# 2DD-17-mk-2_0.net
KiCad netlist of a schematic drawn in EAGLE
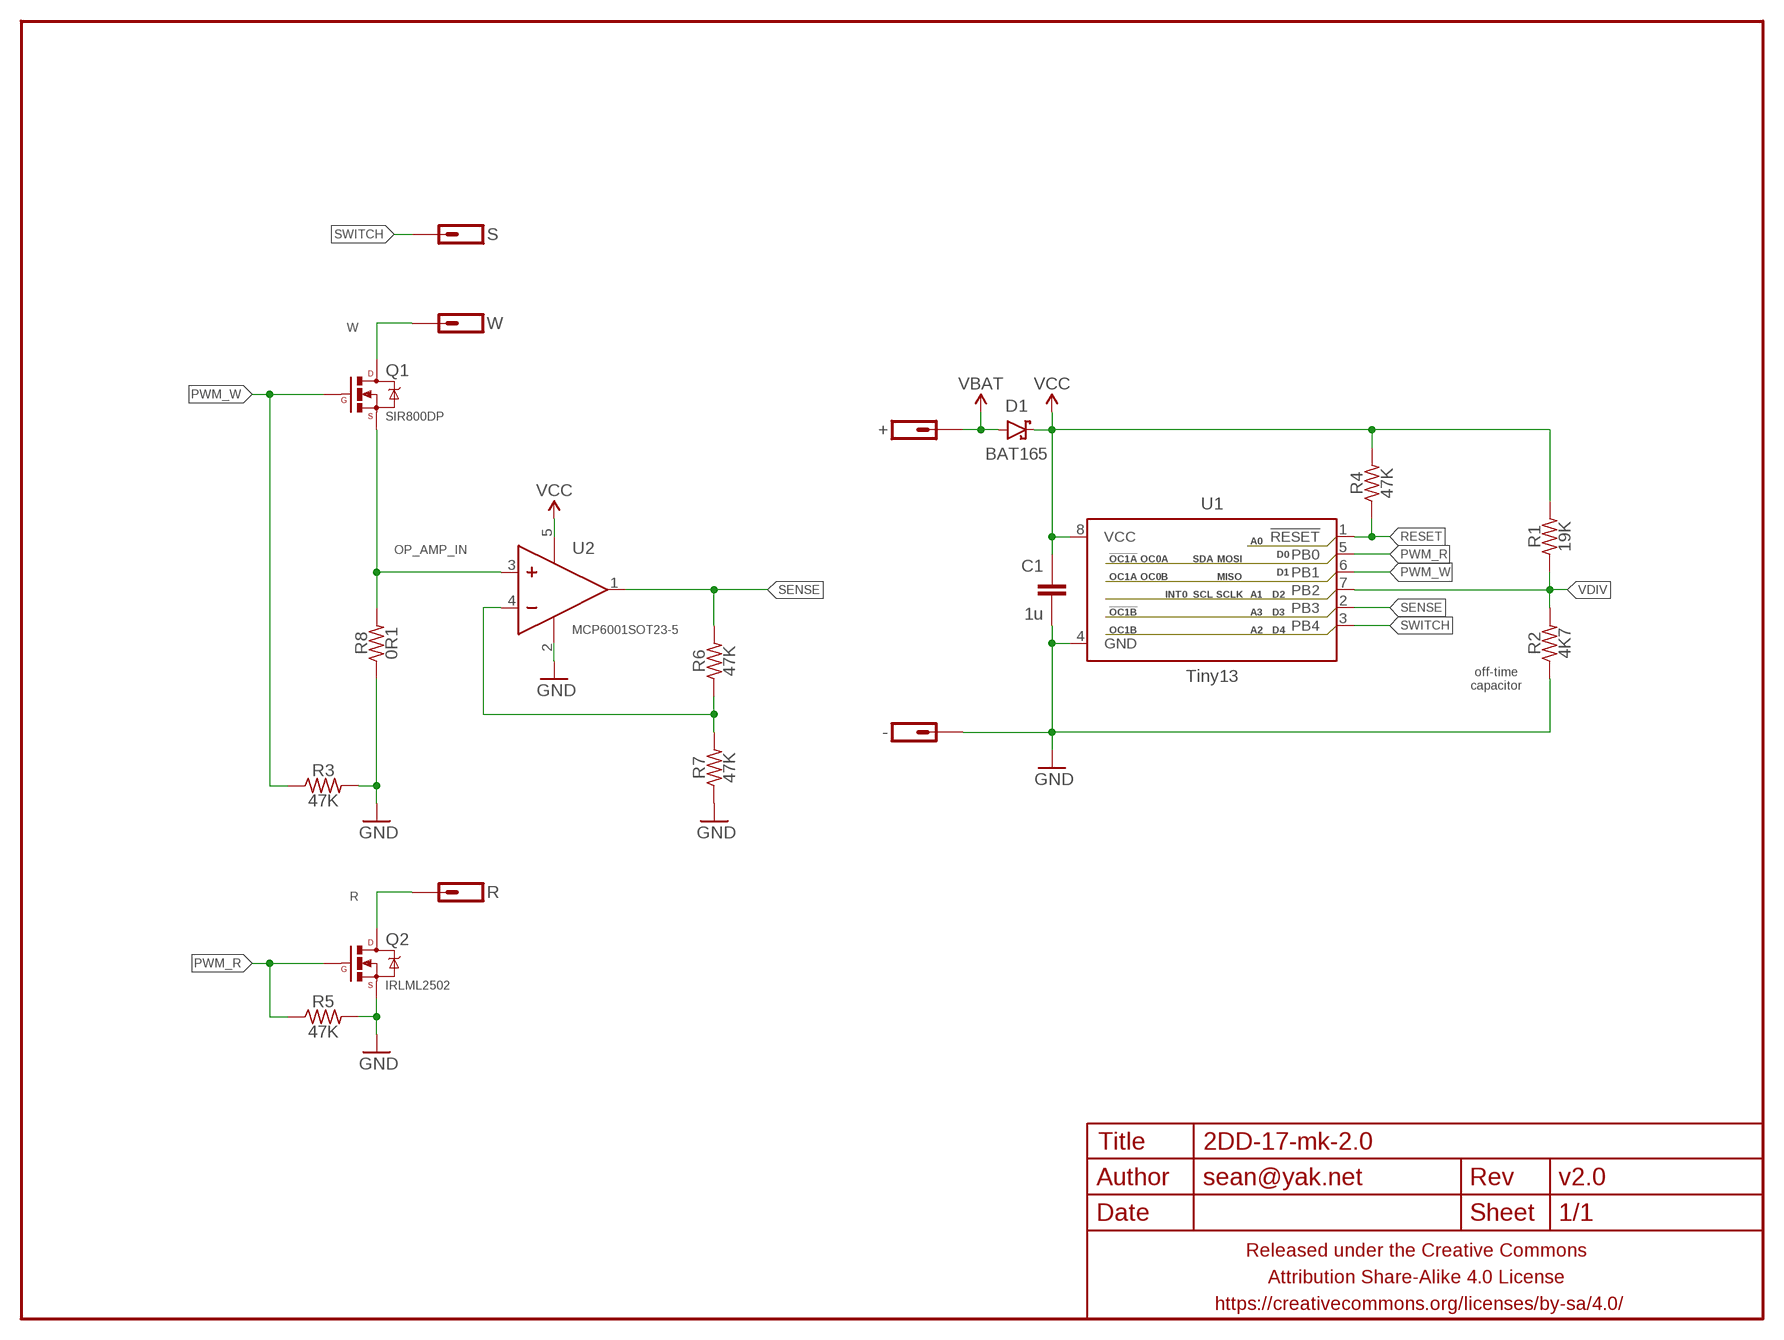
[diagram p0: schematic, sheet 1]

(export (version "E")
  (design (tool "Eeschema 10.0.6"))
  (components
    (comp (ref "+")
      (value "M01PTH-1MM-CIR-NS")
      (footprint "eagle-import:1X01-1MM-CIR-NS")
      (libsource (lib "eagle-import") (part "M01PTH-1MM-CIR-NS"))
    )
    (comp (ref "-")
      (value "M01NOT-A-VIA-NOPE")
      (footprint "eagle-import:1X01_NOSILK_NOSTOP")
      (libsource (lib "eagle-import") (part "M01NOT-A-VIA-NOPE"))
    )
    (comp (ref "C1")
      (value "1u")
      (footprint "eagle-import:C0402")
      (libsource (lib "eagle-import") (part "CAPACITOR-CERAMICC0402"))
    )
    (comp (ref "D1")
      (value "BAT165")
      (footprint "eagle-import:SOD323-SCHOTTKY")
      (libsource (lib "eagle-import") (part "DIODE-SCHOTTKYSOD323"))
    )
    (comp (ref "FRAME1")
      (value "FRAME-LETTERNO_PACKAGE")
      (footprint "eagle-import:DUMMY")
      (fields (field (name "DESIGNER") "sean@yak.net") (field (name "VERSION") "v2.0"))
      (libsource (lib "eagle-import") (part "FRAME-LETTERNO_PACKAGE"))
    )
    (comp (ref "Q1")
      (value "SIR800DP")
      (footprint "eagle-import:POWERPACK-SO-8")
      (libsource (lib "eagle-import") (part "MOSFET-NCHANNELSIR800DP"))
    )
    (comp (ref "Q2")
      (value "IRLML2502")
      (footprint "eagle-import:SOT23-CLOSER")
      (libsource (lib "eagle-import") (part "MOSFET-NCHANNELIRLML2502-SMOL"))
    )
    (comp (ref "R")
      (value "M01SMD-1.25MM-DIA")
      (footprint "eagle-import:1X01-SMD-1.25MM-DIA-NS")
      (libsource (lib "eagle-import") (part "M01SMD-1.25MM-DIA"))
    )
    (comp (ref "R1")
      (value "19K")
      (footprint "eagle-import:R0402")
      (libsource (lib "eagle-import") (part "RESISTORR0402"))
    )
    (comp (ref "R2")
      (value "4K7")
      (footprint "eagle-import:R0402")
      (libsource (lib "eagle-import") (part "RESISTORR0402"))
    )
    (comp (ref "R3")
      (value "47K")
      (footprint "eagle-import:R0402")
      (libsource (lib "eagle-import") (part "RESISTORR0402"))
    )
    (comp (ref "R4")
      (value "47K")
      (footprint "eagle-import:R0402")
      (libsource (lib "eagle-import") (part "RESISTORR0402"))
    )
    (comp (ref "R5")
      (value "47K")
      (footprint "eagle-import:R0402")
      (libsource (lib "eagle-import") (part "RESISTORR0402"))
    )
    (comp (ref "R6")
      (value "47K")
      (footprint "eagle-import:R0402")
      (libsource (lib "eagle-import") (part "RESISTORR0402"))
    )
    (comp (ref "R7")
      (value "47K")
      (footprint "eagle-import:R0402")
      (libsource (lib "eagle-import") (part "RESISTORR0402"))
    )
    (comp (ref "R8")
      (value "0R1")
      (footprint "eagle-import:R0805")
      (libsource (lib "eagle-import") (part "RESISTORR0805"))
    )
    (comp (ref "S")
      (value "M01SMD-1.25MM-DIA")
      (footprint "eagle-import:1X01-SMD-1.25MM-DIA-NS")
      (libsource (lib "eagle-import") (part "M01SMD-1.25MM-DIA"))
    )
    (comp (ref "U1")
      (value "Tiny13")
      (footprint "eagle-import:SO08-NARROWER")
      (libsource (lib "eagle-import") (part "ATTINY13SOIC-NARROWPADS"))
    )
    (comp (ref "U2")
      (value "MCP6001SOT23-5")
      (footprint "eagle-import:SOT23-5")
      (libsource (lib "eagle-import") (part "MCP6001SOT23-5"))
    )
    (comp (ref "W")
      (value "M01SMD-1.25MM-DIA")
      (footprint "eagle-import:1X01-SMD-1.25MM-DIA-NS")
      (libsource (lib "eagle-import") (part "M01SMD-1.25MM-DIA"))
    )
  )
  (nets
    (net (code "1") (name "/OP_AMP_IN") (class "Default")
      (node (ref "Q1") (pin "1") (pinfunction "S_1") (pintype "passive"))
      (node (ref "Q1") (pin "2") (pinfunction "S_2") (pintype "passive"))
      (node (ref "Q1") (pin "3") (pinfunction "S_3") (pintype "passive"))
      (node (ref "R8") (pin "2") (pinfunction "2_2") (pintype "passive"))
      (node (ref "U2") (pin "3") (pinfunction "IN+_3") (pintype "input"))
    )
    (net (code "2") (name "/R") (class "Default")
      (node (ref "Q2") (pin "3") (pinfunction "D_3") (pintype "passive"))
      (node (ref "R") (pin "P$1") (pinfunction "1_P$1") (pintype "passive"))
    )
    (net (code "3") (name "/W") (class "Default")
      (node (ref "Q1") (pin "5678") (pinfunction "D_5678") (pintype "passive"))
      (node (ref "W") (pin "P$1") (pinfunction "1_P$1") (pintype "passive"))
    )
    (net (code "4") (name "GND") (class "Default")
      (node (ref "-") (pin "P$1") (pinfunction "1_P$1") (pintype "passive"))
      (node (ref "C1") (pin "2") (pinfunction "2_2") (pintype "passive"))
      (node (ref "Q2") (pin "2") (pinfunction "S_2") (pintype "passive"))
      (node (ref "R2") (pin "1") (pinfunction "1_1") (pintype "passive"))
      (node (ref "R3") (pin "2") (pinfunction "2_2") (pintype "passive"))
      (node (ref "R5") (pin "2") (pinfunction "2_2") (pintype "passive"))
      (node (ref "R7") (pin "1") (pinfunction "1_1") (pintype "passive"))
      (node (ref "R8") (pin "1") (pinfunction "1_1") (pintype "passive"))
      (node (ref "U1") (pin "4") (pinfunction "GND_4") (pintype "bidirectional"))
      (node (ref "U2") (pin "2") (pinfunction "V-_2") (pintype "power_in"))
    )
    (net (code "5") (name "Net-(U2-IN-)") (class "Default")
      (node (ref "R6") (pin "1") (pinfunction "1_1") (pintype "passive"))
      (node (ref "R7") (pin "2") (pinfunction "2_2") (pintype "passive"))
      (node (ref "U2") (pin "4") (pinfunction "IN-_4") (pintype "input"))
    )
    (net (code "6") (name "PWM_R") (class "Default")
      (node (ref "Q2") (pin "1") (pinfunction "G_1") (pintype "passive"))
      (node (ref "R5") (pin "1") (pinfunction "1_1") (pintype "passive"))
      (node (ref "U1") (pin "5") (pinfunction "PB0_5") (pintype "bidirectional"))
    )
    (net (code "7") (name "PWM_W") (class "Default")
      (node (ref "Q1") (pin "4") (pinfunction "G_4") (pintype "passive"))
      (node (ref "R3") (pin "1") (pinfunction "1_1") (pintype "passive"))
      (node (ref "U1") (pin "6") (pinfunction "PB1_6") (pintype "bidirectional"))
    )
    (net (code "8") (name "RESET") (class "Default")
      (node (ref "R4") (pin "1") (pinfunction "1_1") (pintype "passive"))
      (node (ref "U1") (pin "1") (pinfunction "~{RESET}_1") (pintype "bidirectional"))
    )
    (net (code "9") (name "SENSE") (class "Default")
      (node (ref "R6") (pin "2") (pinfunction "2_2") (pintype "passive"))
      (node (ref "U1") (pin "2") (pinfunction "PB3_2") (pintype "bidirectional"))
      (node (ref "U2") (pin "1") (pinfunction "OUT_1") (pintype "output"))
    )
    (net (code "10") (name "SWITCH") (class "Default")
      (node (ref "S") (pin "P$1") (pinfunction "1_P$1") (pintype "passive"))
      (node (ref "U1") (pin "3") (pinfunction "PB4_3") (pintype "bidirectional"))
    )
    (net (code "11") (name "VBAT") (class "Default")
      (node (ref "+") (pin "1") (pinfunction "1_1") (pintype "passive"))
      (node (ref "D1") (pin "A") (pinfunction "A_A") (pintype "passive"))
    )
    (net (code "12") (name "VCC") (class "Default")
      (node (ref "C1") (pin "1") (pinfunction "1_1") (pintype "passive"))
      (node (ref "D1") (pin "C") (pinfunction "C_C") (pintype "passive"))
      (node (ref "R1") (pin "2") (pinfunction "2_2") (pintype "passive"))
      (node (ref "R4") (pin "2") (pinfunction "2_2") (pintype "passive"))
      (node (ref "U1") (pin "8") (pinfunction "VCC_8") (pintype "bidirectional"))
      (node (ref "U2") (pin "5") (pinfunction "V+_5") (pintype "power_in"))
    )
    (net (code "13") (name "VDIV") (class "Default")
      (node (ref "R1") (pin "1") (pinfunction "1_1") (pintype "passive"))
      (node (ref "R2") (pin "2") (pinfunction "2_2") (pintype "passive"))
      (node (ref "U1") (pin "7") (pinfunction "PB2_7") (pintype "bidirectional"))
    )
  )
)
